# Modulo_BL652.net
KiCad netlist of a schematic drawn in Altium Designer
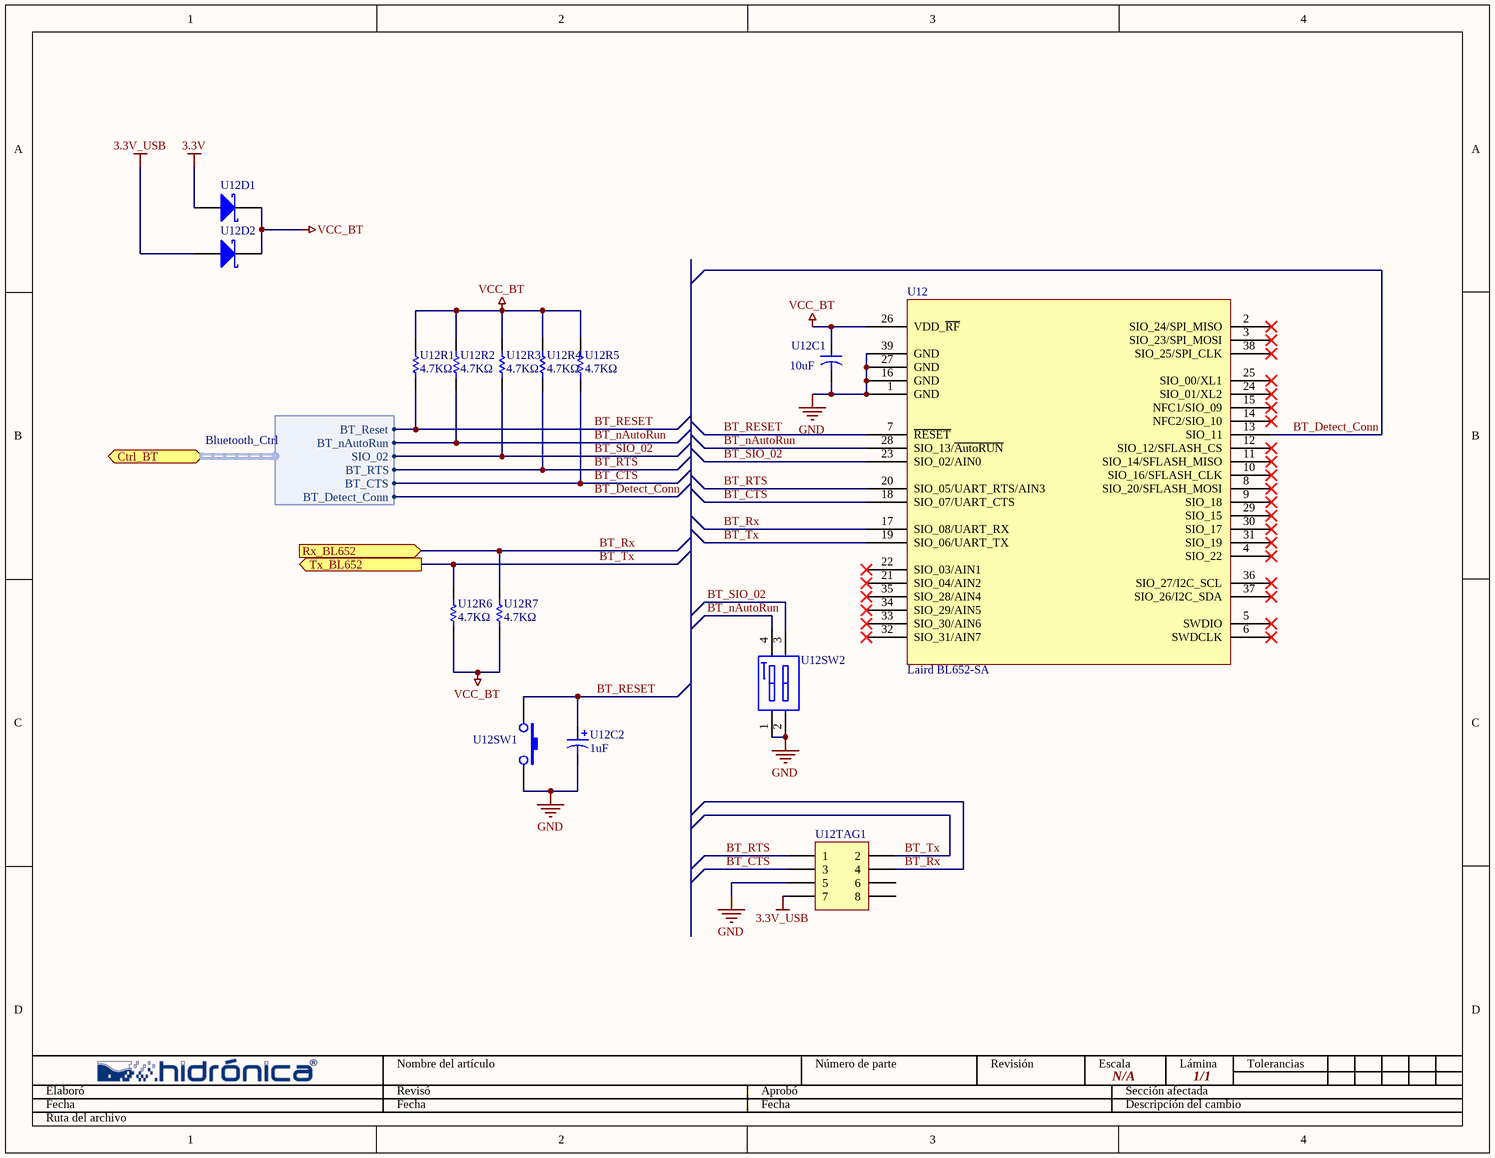
[diagram p0: Modulo BL652.SchDoc]

(export (version "E")
  (design (tool "Eeschema 10.0.6"))
  (components
    (comp (ref "U12")
      (value "Laird BL652-SA")
      (footprint "BT652")
      (fields
        (field (name "MANUFACTURER") "Laird")
        (field (name "MANUFACTURER PART NUMBER") "BL652-SA-01-T/R")
      )
      (libsource (lib "Laird BL652") (part "BL652_SA"))
    )
    (comp (ref "U12C1")
      (value "10uF")
      (footprint "1206-CAP")
      (description "CAP TANTALUM 10UF 6.3V 10% SMD")
      (fields
        (field (name "MANUFACTURER") "Kemet")
        (field (name "MANUFACTURER PART NUMBER") "T491A106K010AT")
      )
      (libsource (lib "Miscellaneous Devices") (part "Cap2"))
    )
    (comp (ref "U12C2")
      (value "1uF")
      (footprint "0805-tan")
      (description "AVX - TACU105M016X - CAP TANT 1UF, 16V, 7.5OHM, 0805")
      (fields
        (field (name "MANUFACTURER") "AVX Corporation")
        (field (name "MANUFACTURER PART NUMBER") "TAJR105K010RNJ")
      )
      (libsource (lib "Miscellaneous Devices") (part "Cap Pol1"))
    )
    (comp (ref "U12D1")
      (value "NSR0320MW2T1G")
      (footprint "SOD-323")
      (description "DIODE SCHOTTKY 1A 20V SOD-323")
      (fields (field (name "MANUFACTURER") "ON Semiconductor"))
      (libsource (lib "IR Discrete Rectifier - Schottky") (part "10MQ060N"))
    )
    (comp (ref "U12D2")
      (value "NSR0320MW2T1G")
      (footprint "SOD-323")
      (description "DIODE SCHOTTKY 1A 20V SOD-323")
      (fields (field (name "MANUFACTURER") "ON Semiconductor"))
      (libsource (lib "IR Discrete Rectifier - Schottky") (part "10MQ060N"))
    )
    (comp (ref "U12R1")
      (value "4.7KΩ")
      (footprint "0805-RES")
      (description "RES SMD 4.7K OHM 5% 1/8W 0805")
      (fields
        (field (name "MANUFACTURER") "Panasonic Electronic Components")
        (field (name "MANUFACTURER PART NUMBER") "ERJ-6GEYJ472V")
      )
      (libsource (lib "Miscellaneous Devices") (part "Res1"))
    )
    (comp (ref "U12R2")
      (value "4.7KΩ")
      (footprint "0805-RES")
      (description "RES SMD 4.7K OHM 5% 1/8W 0805")
      (fields
        (field (name "MANUFACTURER") "Panasonic Electronic Components")
        (field (name "MANUFACTURER PART NUMBER") "ERJ-6GEYJ472V")
      )
      (libsource (lib "Miscellaneous Devices") (part "Res1"))
    )
    (comp (ref "U12R3")
      (value "4.7KΩ")
      (footprint "0805-RES")
      (description "RES SMD 4.7K OHM 5% 1/8W 0805")
      (fields
        (field (name "MANUFACTURER") "Panasonic Electronic Components")
        (field (name "MANUFACTURER PART NUMBER") "ERJ-6GEYJ472V")
      )
      (libsource (lib "Miscellaneous Devices") (part "Res1"))
    )
    (comp (ref "U12R4")
      (value "4.7KΩ")
      (footprint "0805-RES")
      (description "RES SMD 4.7K OHM 5% 1/8W 0805")
      (fields
        (field (name "MANUFACTURER") "Panasonic Electronic Components")
        (field (name "MANUFACTURER PART NUMBER") "ERJ-6GEYJ472V")
      )
      (libsource (lib "Miscellaneous Devices") (part "Res1"))
    )
    (comp (ref "U12R5")
      (value "4.7KΩ")
      (footprint "0805-RES")
      (description "RES SMD 4.7K OHM 5% 1/8W 0805")
      (fields
        (field (name "MANUFACTURER") "Panasonic Electronic Components")
        (field (name "MANUFACTURER PART NUMBER") "ERJ-6GEYJ472V")
      )
      (libsource (lib "Miscellaneous Devices") (part "Res1"))
    )
    (comp (ref "U12R6")
      (value "4.7KΩ")
      (footprint "0805-RES")
      (description "RES SMD 4.7K OHM 5% 1/8W 0805")
      (fields
        (field (name "MANUFACTURER") "Panasonic Electronic Components")
        (field (name "MANUFACTURER PART NUMBER") "ERJ-6GEYJ472V")
      )
      (libsource (lib "Miscellaneous Devices") (part "Res1"))
    )
    (comp (ref "U12R7")
      (value "4.7KΩ")
      (footprint "0805-RES")
      (description "RES SMD 4.7K OHM 5% 1/8W 0805")
      (fields
        (field (name "MANUFACTURER") "Panasonic Electronic Components")
        (field (name "MANUFACTURER PART NUMBER") "ERJ-6GEYJ472V")
      )
      (libsource (lib "Miscellaneous Devices") (part "Res1"))
    )
    (comp (ref "U12SW1")
      (value "~")
      (footprint "430 473 031 826")
      (description "SWITCH TACTILE SPST-NO 0.02A 15V SMT")
      (fields
        (field (name "MANUFACTURER PART NUMBER") "EVQ-Q2K03W")
        (field (name "MANUFACTURER") "Panasonic Electronic Components")
      )
      (libsource (lib "*") (part "SW-PB"))
    )
    (comp (ref "U12SW2")
      (value "SW DIP-2")
      (footprint "CHS-02TA")
      (description "SWITCH SLIDE DIP SPST 100MA 6V")
      (fields
        (field (name "MANUFACTURER PART NUMBER") "CHS-02TA")
        (field (name "MANUFACTURER") "Nidec Copal Electronics")
      )
      (libsource (lib "Miscellaneous Devices") (part "SW DIP-2"))
    )
    (comp (ref "U12TAG1")
      (value "Header 4X2")
      (footprint "690367290876")
      (description "Female SMT Straight Connector with Latch and with Polarization WR-MM 8-Pin")
      (fields (field (name "MANUFACTURER PART NUMBER") "690 367 290 876"))
      (libsource (lib "Miscellaneous Connectors") (part "Header 4X2"))
    )
  )
  (nets
    (net (code "2") (name "/BT_CTS") (class "Default")
      (node (ref "U12") (pin "18") (pinfunction "SIO_07/UART_CTS_18") (pintype "passive"))
      (node (ref "U12R5") (pin "2") (pinfunction "2_2") (pintype "passive"))
      (node (ref "U12TAG1") (pin "3") (pinfunction "3_3") (pintype "passive"))
    )
    (net (code "3") (name "/BT_Detect_Conn") (class "Default")
      (node (ref "U12") (pin "13") (pinfunction "SIO_11_13") (pintype "passive"))
    )
    (net (code "4") (name "/BT_RESET") (class "Default")
      (node (ref "U12") (pin "7") (pinfunction "~{RESET}_7") (pintype "passive"))
      (node (ref "U12C2") (pin "1") (pinfunction "1_1") (pintype "passive"))
      (node (ref "U12R1") (pin "2") (pinfunction "2_2") (pintype "passive"))
      (node (ref "U12SW1") (pin "1") (pinfunction "1_1") (pintype "passive"))
    )
    (net (code "5") (name "/BT_RTS") (class "Default")
      (node (ref "U12") (pin "20") (pinfunction "SIO_05/UART_RTS/AIN3_20") (pintype "passive"))
      (node (ref "U12R4") (pin "2") (pinfunction "2_2") (pintype "passive"))
      (node (ref "U12TAG1") (pin "1") (pinfunction "1_1") (pintype "passive"))
    )
    (net (code "6") (name "/BT_Rx") (class "Default")
      (node (ref "U12") (pin "17") (pinfunction "SIO_08/UART_RX_17") (pintype "passive"))
      (node (ref "U12R7") (pin "1") (pinfunction "1_1") (pintype "passive"))
      (node (ref "U12TAG1") (pin "4") (pinfunction "4_4") (pintype "passive"))
    )
    (net (code "7") (name "/BT_SIO_02") (class "Default")
      (node (ref "U12") (pin "23") (pinfunction "SIO_02/AIN0_23") (pintype "passive"))
      (node (ref "U12R3") (pin "2") (pinfunction "2_2") (pintype "passive"))
      (node (ref "U12SW2") (pin "3") (pinfunction "B2_3") (pintype "passive"))
    )
    (net (code "8") (name "/BT_Tx") (class "Default")
      (node (ref "U12") (pin "19") (pinfunction "SIO_06/UART_TX_19") (pintype "passive"))
      (node (ref "U12R6") (pin "1") (pinfunction "1_1") (pintype "passive"))
      (node (ref "U12TAG1") (pin "2") (pinfunction "2_2") (pintype "passive"))
    )
    (net (code "9") (name "/BT_nAutoRun") (class "Default")
      (node (ref "U12") (pin "28") (pinfunction "SIO_13/~{AutoRUN}_28") (pintype "passive"))
      (node (ref "U12R2") (pin "2") (pinfunction "2_2") (pintype "passive"))
      (node (ref "U12SW2") (pin "4") (pinfunction "B1_4") (pintype "passive"))
    )
    (net (code "11") (name "3.3V") (class "Default")
      (node (ref "U12D1") (pin "1") (pinfunction "A_1") (pintype "passive"))
    )
    (net (code "12") (name "3.3V_USB") (class "Default")
      (node (ref "U12D2") (pin "1") (pinfunction "A_1") (pintype "passive"))
      (node (ref "U12TAG1") (pin "7") (pinfunction "7_7") (pintype "passive"))
    )
    (net (code "13") (name "GND") (class "Default")
      (node (ref "U12") (pin "1") (pinfunction "GND_1") (pintype "passive"))
      (node (ref "U12") (pin "16") (pinfunction "GND_16") (pintype "passive"))
      (node (ref "U12") (pin "27") (pinfunction "GND_27") (pintype "passive"))
      (node (ref "U12") (pin "39") (pinfunction "GND_39") (pintype "passive"))
      (node (ref "U12C1") (pin "2") (pinfunction "2_2") (pintype "passive"))
      (node (ref "U12C2") (pin "2") (pinfunction "2_2") (pintype "passive"))
      (node (ref "U12SW1") (pin "2") (pinfunction "2_2") (pintype "passive"))
      (node (ref "U12SW2") (pin "1") (pinfunction "A1_1") (pintype "passive"))
      (node (ref "U12SW2") (pin "2") (pinfunction "A2_2") (pintype "passive"))
      (node (ref "U12TAG1") (pin "5") (pinfunction "5_5") (pintype "passive"))
    )
    (net (code "14") (name "VCC_BT") (class "Default")
      (node (ref "U12") (pin "26") (pinfunction "VDD_~{RF}_26") (pintype "passive"))
      (node (ref "U12C1") (pin "1") (pinfunction "1_1") (pintype "passive"))
      (node (ref "U12D1") (pin "2") (pinfunction "K_2") (pintype "passive"))
      (node (ref "U12D2") (pin "2") (pinfunction "K_2") (pintype "passive"))
      (node (ref "U12R1") (pin "1") (pinfunction "1_1") (pintype "passive"))
      (node (ref "U12R2") (pin "1") (pinfunction "1_1") (pintype "passive"))
      (node (ref "U12R3") (pin "1") (pinfunction "1_1") (pintype "passive"))
      (node (ref "U12R4") (pin "1") (pinfunction "1_1") (pintype "passive"))
      (node (ref "U12R5") (pin "1") (pinfunction "1_1") (pintype "passive"))
      (node (ref "U12R6") (pin "2") (pinfunction "2_2") (pintype "passive"))
      (node (ref "U12R7") (pin "2") (pinfunction "2_2") (pintype "passive"))
    )
    (net (code "15") (name "unconnected-(U12-NFC1{slash}SIO_09-Pad15)") (class "Default")
      (node (ref "U12") (pin "15") (pinfunction "NFC1/SIO_09_15") (pintype "passive+no_connect"))
    )
    (net (code "16") (name "unconnected-(U12-NFC2{slash}SIO_10-Pad14)") (class "Default")
      (node (ref "U12") (pin "14") (pinfunction "NFC2/SIO_10_14") (pintype "passive+no_connect"))
    )
    (net (code "17") (name "unconnected-(U12-SIO_00{slash}XL1-Pad25)") (class "Default")
      (node (ref "U12") (pin "25") (pinfunction "SIO_00/XL1_25") (pintype "passive+no_connect"))
    )
    (net (code "18") (name "unconnected-(U12-SIO_01{slash}XL2-Pad24)") (class "Default")
      (node (ref "U12") (pin "24") (pinfunction "SIO_01/XL2_24") (pintype "passive+no_connect"))
    )
    (net (code "19") (name "unconnected-(U12-SIO_03{slash}AIN1-Pad22)") (class "Default")
      (node (ref "U12") (pin "22") (pinfunction "SIO_03/AIN1_22") (pintype "passive+no_connect"))
    )
    (net (code "20") (name "unconnected-(U12-SIO_04{slash}AIN2-Pad21)") (class "Default")
      (node (ref "U12") (pin "21") (pinfunction "SIO_04/AIN2_21") (pintype "passive+no_connect"))
    )
    (net (code "21") (name "unconnected-(U12-SIO_12{slash}SFLASH_CS-Pad12)") (class "Default")
      (node (ref "U12") (pin "12") (pinfunction "SIO_12/SFLASH_CS_12") (pintype "passive+no_connect"))
    )
    (net (code "22") (name "unconnected-(U12-SIO_14{slash}SFLASH_MISO-Pad11)") (class "Default")
      (node (ref "U12") (pin "11") (pinfunction "SIO_14/SFLASH_MISO_11") (pintype "passive+no_connect"))
    )
    (net (code "23") (name "unconnected-(U12-SIO_15-Pad29)") (class "Default")
      (node (ref "U12") (pin "29") (pinfunction "SIO_15_29") (pintype "passive+no_connect"))
    )
    (net (code "24") (name "unconnected-(U12-SIO_16{slash}SFLASH_CLK-Pad10)") (class "Default")
      (node (ref "U12") (pin "10") (pinfunction "SIO_16/SFLASH_CLK_10") (pintype "passive+no_connect"))
    )
    (net (code "25") (name "unconnected-(U12-SIO_17-Pad30)") (class "Default")
      (node (ref "U12") (pin "30") (pinfunction "SIO_17_30") (pintype "passive+no_connect"))
    )
    (net (code "26") (name "unconnected-(U12-SIO_18-Pad9)") (class "Default")
      (node (ref "U12") (pin "9") (pinfunction "SIO_18_9") (pintype "passive+no_connect"))
    )
    (net (code "27") (name "unconnected-(U12-SIO_19-Pad31)") (class "Default")
      (node (ref "U12") (pin "31") (pinfunction "SIO_19_31") (pintype "passive+no_connect"))
    )
    (net (code "28") (name "unconnected-(U12-SIO_20{slash}SFLASH_MOSI-Pad8)") (class "Default")
      (node (ref "U12") (pin "8") (pinfunction "SIO_20/SFLASH_MOSI_8") (pintype "passive+no_connect"))
    )
    (net (code "29") (name "unconnected-(U12-SIO_22-Pad4)") (class "Default")
      (node (ref "U12") (pin "4") (pinfunction "SIO_22_4") (pintype "passive+no_connect"))
    )
    (net (code "30") (name "unconnected-(U12-SIO_23{slash}SPI_MOSI-Pad3)") (class "Default")
      (node (ref "U12") (pin "3") (pinfunction "SIO_23/SPI_MOSI_3") (pintype "passive+no_connect"))
    )
    (net (code "31") (name "unconnected-(U12-SIO_24{slash}SPI_MISO-Pad2)") (class "Default")
      (node (ref "U12") (pin "2") (pinfunction "SIO_24/SPI_MISO_2") (pintype "passive+no_connect"))
    )
    (net (code "32") (name "unconnected-(U12-SIO_25{slash}SPI_CLK-Pad38)") (class "Default")
      (node (ref "U12") (pin "38") (pinfunction "SIO_25/SPI_CLK_38") (pintype "passive+no_connect"))
    )
    (net (code "33") (name "unconnected-(U12-SIO_26{slash}I2C_SDA-Pad37)") (class "Default")
      (node (ref "U12") (pin "37") (pinfunction "SIO_26/I2C_SDA_37") (pintype "passive+no_connect"))
    )
    (net (code "34") (name "unconnected-(U12-SIO_27{slash}I2C_SCL-Pad36)") (class "Default")
      (node (ref "U12") (pin "36") (pinfunction "SIO_27/I2C_SCL_36") (pintype "passive+no_connect"))
    )
    (net (code "35") (name "unconnected-(U12-SIO_28{slash}AIN4-Pad35)") (class "Default")
      (node (ref "U12") (pin "35") (pinfunction "SIO_28/AIN4_35") (pintype "passive+no_connect"))
    )
    (net (code "36") (name "unconnected-(U12-SIO_29{slash}AIN5-Pad34)") (class "Default")
      (node (ref "U12") (pin "34") (pinfunction "SIO_29/AIN5_34") (pintype "passive+no_connect"))
    )
    (net (code "37") (name "unconnected-(U12-SIO_30{slash}AIN6-Pad33)") (class "Default")
      (node (ref "U12") (pin "33") (pinfunction "SIO_30/AIN6_33") (pintype "passive+no_connect"))
    )
    (net (code "38") (name "unconnected-(U12-SIO_31{slash}AIN7-Pad32)") (class "Default")
      (node (ref "U12") (pin "32") (pinfunction "SIO_31/AIN7_32") (pintype "passive+no_connect"))
    )
    (net (code "39") (name "unconnected-(U12-SWDCLK-Pad6)") (class "Default")
      (node (ref "U12") (pin "6") (pinfunction "SWDCLK_6") (pintype "passive+no_connect"))
    )
    (net (code "40") (name "unconnected-(U12-SWDIO-Pad5)") (class "Default")
      (node (ref "U12") (pin "5") (pinfunction "SWDIO_5") (pintype "passive+no_connect"))
    )
    (net (code "41") (name "unconnected-(U12TAG1-Pad6)") (class "Default")
      (node (ref "U12TAG1") (pin "6") (pinfunction "6_6") (pintype "passive"))
    )
    (net (code "42") (name "unconnected-(U12TAG1-Pad8)") (class "Default")
      (node (ref "U12TAG1") (pin "8") (pinfunction "8_8") (pintype "passive"))
    )
  )
)
